# Daughter2_routed.net
KiCad netlist of a schematic drawn in EAGLE
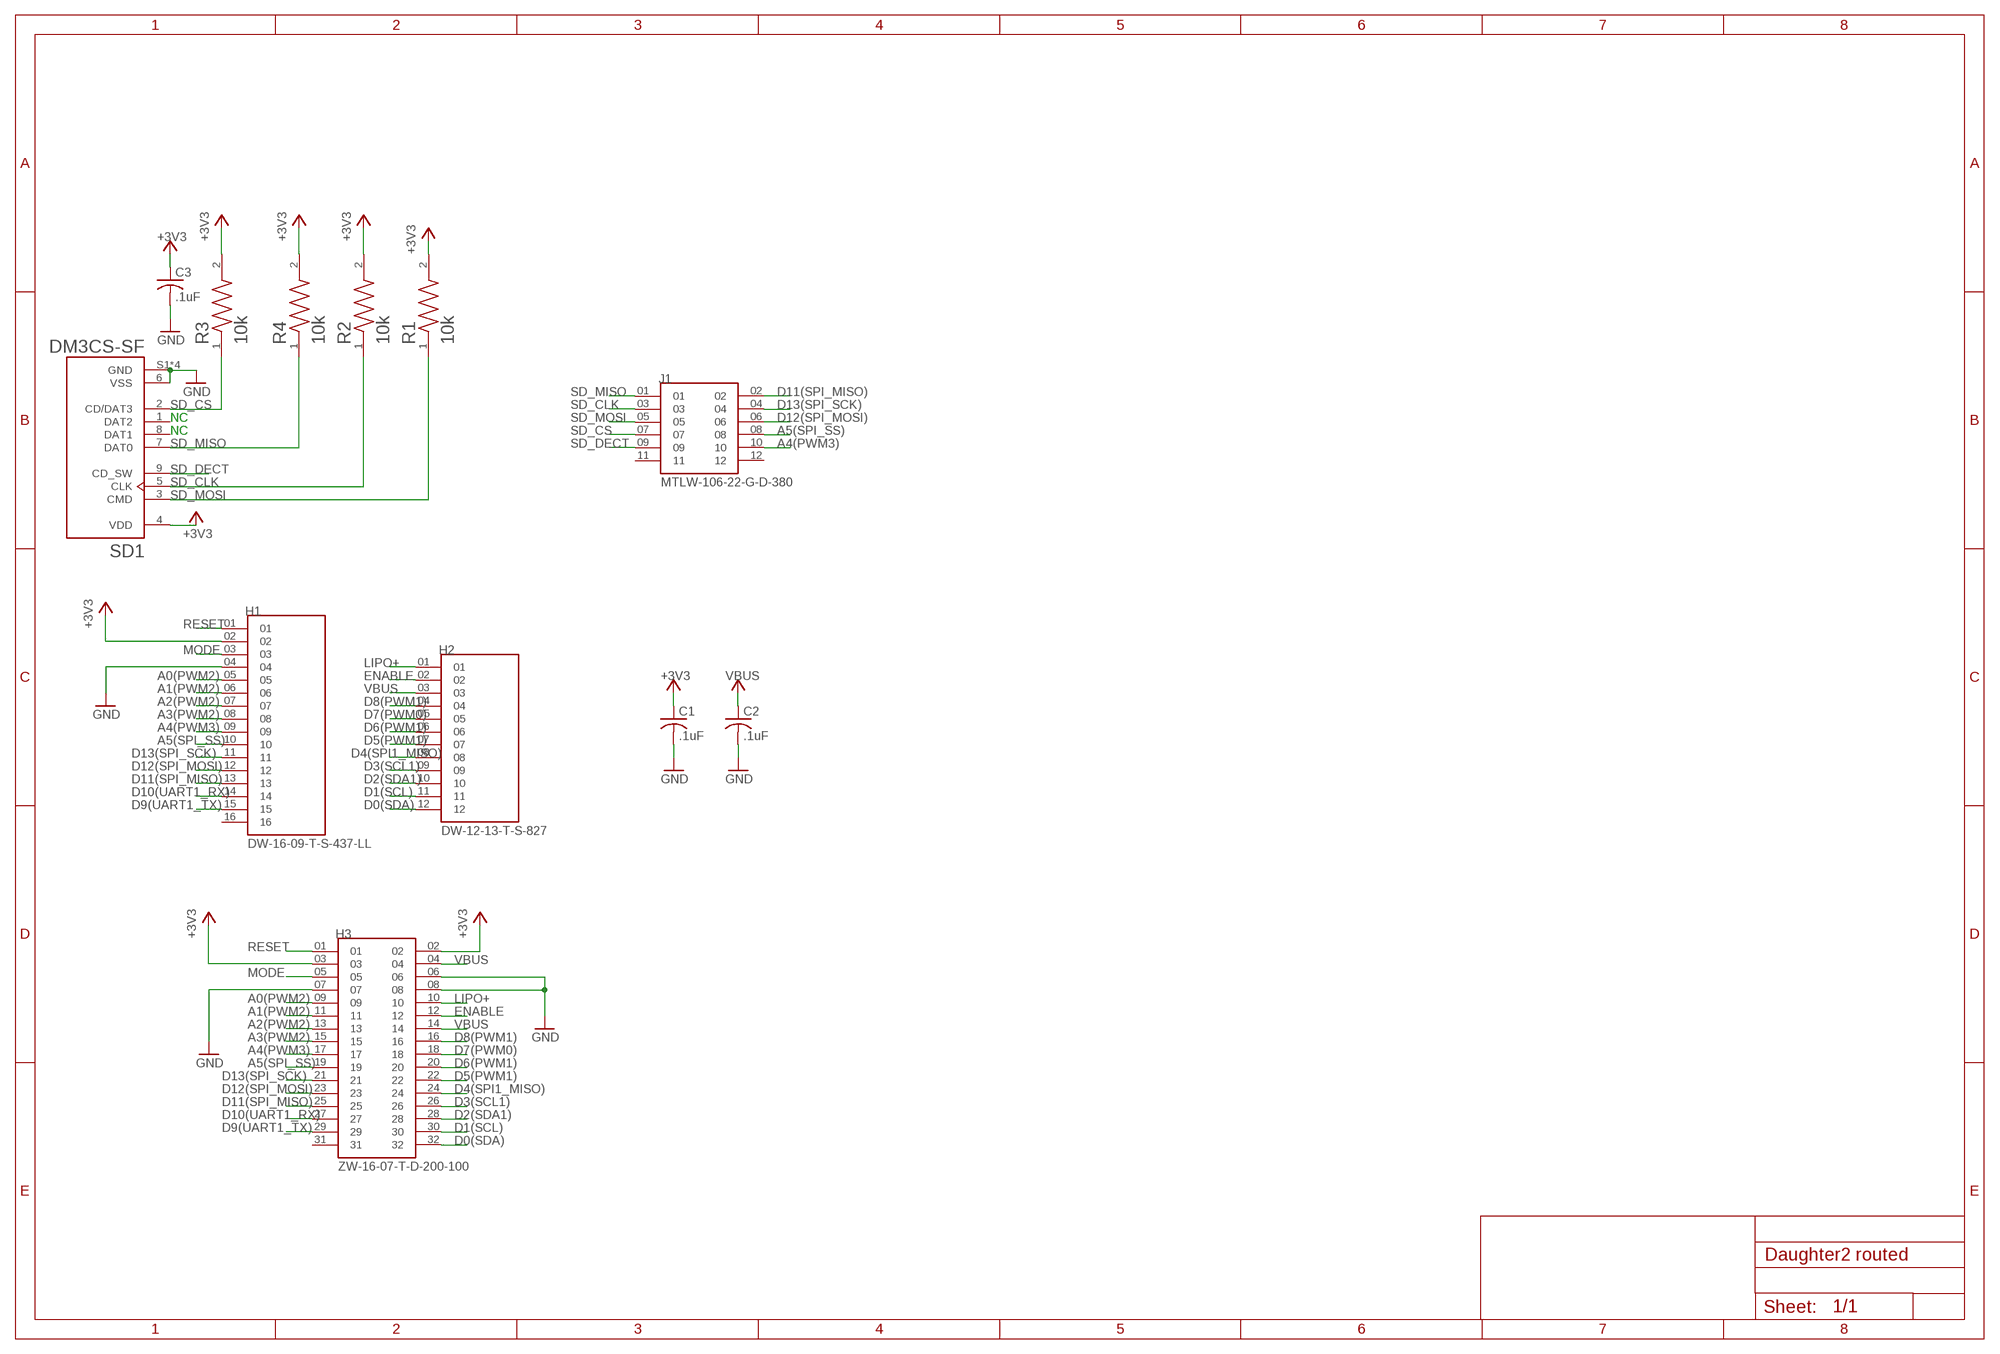
[diagram p0: schematic, sheet 1]

(export (version "E")
  (design (tool "Eeschema 10.0.6"))
  (components
    (comp (ref "C1")
      (value ".1uF")
      (footprint "eagle-import:C025-030X050")
      (libsource (lib "eagle-import") (part "C-US025-030X050"))
    )
    (comp (ref "C2")
      (value ".1uF")
      (footprint "eagle-import:C025-030X050")
      (libsource (lib "eagle-import") (part "C-US025-030X050"))
    )
    (comp (ref "C3")
      (value ".1uF")
      (footprint "eagle-import:C025-030X050")
      (libsource (lib "eagle-import") (part "C-US025-030X050"))
    )
    (comp (ref "H1")
      (value "DW-16-09-T-S-437-LL")
      (footprint "eagle-import:SAMTEC_DW-16-09-T-S-437-LL")
      (fields (field (name "MF") "Samtec"))
      (libsource (lib "eagle-import") (part "DW-16-09-T-S-437-LL"))
    )
    (comp (ref "H2")
      (value "DW-12-13-T-S-827")
      (footprint "eagle-import:SAMTEC_DW-12-13-T-S-827")
      (fields (field (name "MF") "Samtec Inc."))
      (libsource (lib "eagle-import") (part "DW-12-13-T-S-827"))
    )
    (comp (ref "H3")
      (value "ZW-16-07-T-D-200-100")
      (footprint "eagle-import:SAMTEC_ZW-16-07-T-D-200-100")
      (fields (field (name "MF") "Samtec Inc."))
      (libsource (lib "eagle-import") (part "ZW-16-07-T-D-200-100"))
    )
    (comp (ref "J1")
      (value "MTLW-106-22-G-D-380")
      (footprint "eagle-import:SAMTEC_MTLW-106-22-G-D-380")
      (fields (field (name "MF") "Samtec"))
      (libsource (lib "eagle-import") (part "MTLW-106-22-G-D-380"))
    )
    (comp (ref "R1")
      (value "10k")
      (footprint "eagle-import:RESAD700W45L350D185")
      (fields
        (field (name "COMMENT") "1623927-4")
        (field (name "MF") "TE Connectivity")
        (field (name "TOLERANCE") "5%")
      )
      (libsource (lib "eagle-import") (part "1623927-4"))
    )
    (comp (ref "R2")
      (value "10k")
      (footprint "eagle-import:RESAD700W45L350D185")
      (fields
        (field (name "COMMENT") "1623927-4")
        (field (name "MF") "TE Connectivity")
        (field (name "TOLERANCE") "5%")
      )
      (libsource (lib "eagle-import") (part "1623927-4"))
    )
    (comp (ref "R3")
      (value "10k")
      (footprint "eagle-import:RESAD700W45L350D185")
      (fields
        (field (name "COMMENT") "1623927-4")
        (field (name "MF") "TE Connectivity")
        (field (name "TOLERANCE") "5%")
      )
      (libsource (lib "eagle-import") (part "1623927-4"))
    )
    (comp (ref "R4")
      (value "10k")
      (footprint "eagle-import:RESAD700W45L350D185")
      (fields
        (field (name "COMMENT") "1623927-4")
        (field (name "MF") "TE Connectivity")
        (field (name "TOLERANCE") "5%")
      )
      (libsource (lib "eagle-import") (part "1623927-4"))
    )
    (comp (ref "SD1")
      (value "DM3CS-SF")
      (footprint "eagle-import:HRS_DM3CS-SF")
      (fields (field (name "MF") "Hirose"))
      (libsource (lib "eagle-import") (part "DM3CS-SF"))
    )
  )
  (nets
    (net (code "1") (name "+3V3") (class "Default")
      (node (ref "C1") (pin "1") (pinfunction "1_1") (pintype "passive"))
      (node (ref "C3") (pin "1") (pinfunction "1_1") (pintype "passive"))
      (node (ref "H1") (pin "02") (pinfunction "02_02") (pintype "passive"))
      (node (ref "H3") (pin "02") (pinfunction "02_02") (pintype "passive"))
      (node (ref "H3") (pin "03") (pinfunction "03_03") (pintype "passive"))
      (node (ref "R1") (pin "2") (pinfunction "2_2") (pintype "passive"))
      (node (ref "R2") (pin "2") (pinfunction "2_2") (pintype "passive"))
      (node (ref "R3") (pin "2") (pinfunction "2_2") (pintype "passive"))
      (node (ref "R4") (pin "2") (pinfunction "2_2") (pintype "passive"))
      (node (ref "SD1") (pin "4") (pinfunction "VDD_4") (pintype "passive"))
    )
    (net (code "2") (name "/A0(PWM2)") (class "Default")
      (node (ref "H1") (pin "05") (pinfunction "05_05") (pintype "passive"))
      (node (ref "H3") (pin "09") (pinfunction "09_09") (pintype "passive"))
    )
    (net (code "3") (name "/A1(PWM2)") (class "Default")
      (node (ref "H1") (pin "06") (pinfunction "06_06") (pintype "passive"))
      (node (ref "H3") (pin "11") (pinfunction "11_11") (pintype "passive"))
    )
    (net (code "4") (name "/A2(PWM2)") (class "Default")
      (node (ref "H1") (pin "07") (pinfunction "07_07") (pintype "passive"))
      (node (ref "H3") (pin "13") (pinfunction "13_13") (pintype "passive"))
    )
    (net (code "5") (name "/A3(PWM2)") (class "Default")
      (node (ref "H1") (pin "08") (pinfunction "08_08") (pintype "passive"))
      (node (ref "H3") (pin "15") (pinfunction "15_15") (pintype "passive"))
    )
    (net (code "6") (name "/A4(PWM3)") (class "Default")
      (node (ref "H1") (pin "09") (pinfunction "09_09") (pintype "passive"))
      (node (ref "H3") (pin "17") (pinfunction "17_17") (pintype "passive"))
      (node (ref "J1") (pin "10") (pinfunction "10_10") (pintype "passive"))
    )
    (net (code "7") (name "/A5(SPI_SS)") (class "Default")
      (node (ref "H1") (pin "10") (pinfunction "10_10") (pintype "passive"))
      (node (ref "H3") (pin "19") (pinfunction "19_19") (pintype "passive"))
      (node (ref "J1") (pin "08") (pinfunction "08_08") (pintype "passive"))
    )
    (net (code "8") (name "/D0(SDA)") (class "Default")
      (node (ref "H2") (pin "12") (pinfunction "12_12") (pintype "passive"))
      (node (ref "H3") (pin "32") (pinfunction "32_32") (pintype "passive"))
    )
    (net (code "9") (name "/D1(SCL)") (class "Default")
      (node (ref "H2") (pin "11") (pinfunction "11_11") (pintype "passive"))
      (node (ref "H3") (pin "30") (pinfunction "30_30") (pintype "passive"))
    )
    (net (code "10") (name "/D2(SDA1)") (class "Default")
      (node (ref "H2") (pin "10") (pinfunction "10_10") (pintype "passive"))
      (node (ref "H3") (pin "28") (pinfunction "28_28") (pintype "passive"))
    )
    (net (code "11") (name "/D3(SCL1)") (class "Default")
      (node (ref "H2") (pin "09") (pinfunction "09_09") (pintype "passive"))
      (node (ref "H3") (pin "26") (pinfunction "26_26") (pintype "passive"))
    )
    (net (code "12") (name "/D4(SPI1_MISO)") (class "Default")
      (node (ref "H2") (pin "08") (pinfunction "08_08") (pintype "passive"))
      (node (ref "H3") (pin "24") (pinfunction "24_24") (pintype "passive"))
    )
    (net (code "13") (name "/D5(PWM1)") (class "Default")
      (node (ref "H2") (pin "07") (pinfunction "07_07") (pintype "passive"))
      (node (ref "H3") (pin "22") (pinfunction "22_22") (pintype "passive"))
    )
    (net (code "14") (name "/D6(PWM1)") (class "Default")
      (node (ref "H2") (pin "06") (pinfunction "06_06") (pintype "passive"))
      (node (ref "H3") (pin "20") (pinfunction "20_20") (pintype "passive"))
    )
    (net (code "15") (name "/D7(PWM0)") (class "Default")
      (node (ref "H2") (pin "05") (pinfunction "05_05") (pintype "passive"))
      (node (ref "H3") (pin "18") (pinfunction "18_18") (pintype "passive"))
    )
    (net (code "16") (name "/D8(PWM1)") (class "Default")
      (node (ref "H2") (pin "04") (pinfunction "04_04") (pintype "passive"))
      (node (ref "H3") (pin "16") (pinfunction "16_16") (pintype "passive"))
    )
    (net (code "17") (name "/D9(UART1_TX)") (class "Default")
      (node (ref "H1") (pin "15") (pinfunction "15_15") (pintype "passive"))
      (node (ref "H3") (pin "29") (pinfunction "29_29") (pintype "passive"))
    )
    (net (code "18") (name "/D10(UART1_RX)") (class "Default")
      (node (ref "H1") (pin "14") (pinfunction "14_14") (pintype "passive"))
      (node (ref "H3") (pin "27") (pinfunction "27_27") (pintype "passive"))
    )
    (net (code "19") (name "/D11(SPI_MISO)") (class "Default")
      (node (ref "H1") (pin "13") (pinfunction "13_13") (pintype "passive"))
      (node (ref "H3") (pin "25") (pinfunction "25_25") (pintype "passive"))
      (node (ref "J1") (pin "02") (pinfunction "02_02") (pintype "passive"))
    )
    (net (code "20") (name "/D12(SPI_MOSI)") (class "Default")
      (node (ref "H1") (pin "12") (pinfunction "12_12") (pintype "passive"))
      (node (ref "H3") (pin "23") (pinfunction "23_23") (pintype "passive"))
      (node (ref "J1") (pin "06") (pinfunction "06_06") (pintype "passive"))
    )
    (net (code "21") (name "/D13(SPI_SCK)") (class "Default")
      (node (ref "H1") (pin "11") (pinfunction "11_11") (pintype "passive"))
      (node (ref "H3") (pin "21") (pinfunction "21_21") (pintype "passive"))
      (node (ref "J1") (pin "04") (pinfunction "04_04") (pintype "passive"))
    )
    (net (code "22") (name "/ENABLE") (class "Default")
      (node (ref "H2") (pin "02") (pinfunction "02_02") (pintype "passive"))
      (node (ref "H3") (pin "12") (pinfunction "12_12") (pintype "passive"))
    )
    (net (code "23") (name "/LIPO+") (class "Default")
      (node (ref "H2") (pin "01") (pinfunction "01_01") (pintype "passive"))
      (node (ref "H3") (pin "10") (pinfunction "10_10") (pintype "passive"))
    )
    (net (code "24") (name "/MODE") (class "Default")
      (node (ref "H1") (pin "03") (pinfunction "03_03") (pintype "passive"))
      (node (ref "H3") (pin "05") (pinfunction "05_05") (pintype "passive"))
    )
    (net (code "25") (name "/RESET") (class "Default")
      (node (ref "H1") (pin "01") (pinfunction "01_01") (pintype "passive"))
      (node (ref "H3") (pin "01") (pinfunction "01_01") (pintype "passive"))
    )
    (net (code "26") (name "/SD_CLK") (class "Default")
      (node (ref "J1") (pin "03") (pinfunction "03_03") (pintype "passive"))
      (node (ref "R2") (pin "1") (pinfunction "1_1") (pintype "passive"))
      (node (ref "SD1") (pin "5") (pinfunction "CLK_5") (pintype "passive"))
    )
    (net (code "27") (name "/SD_CS") (class "Default")
      (node (ref "J1") (pin "07") (pinfunction "07_07") (pintype "passive"))
      (node (ref "R3") (pin "1") (pinfunction "1_1") (pintype "passive"))
      (node (ref "SD1") (pin "2") (pinfunction "CD/DAT3_2") (pintype "passive"))
    )
    (net (code "28") (name "/SD_DECT") (class "Default")
      (node (ref "J1") (pin "09") (pinfunction "09_09") (pintype "passive"))
      (node (ref "SD1") (pin "9") (pinfunction "CD_SW_9") (pintype "passive"))
    )
    (net (code "29") (name "/SD_MISO") (class "Default")
      (node (ref "J1") (pin "01") (pinfunction "01_01") (pintype "passive"))
      (node (ref "R4") (pin "1") (pinfunction "1_1") (pintype "passive"))
      (node (ref "SD1") (pin "7") (pinfunction "DAT0_7") (pintype "passive"))
    )
    (net (code "30") (name "/SD_MOSI") (class "Default")
      (node (ref "J1") (pin "05") (pinfunction "05_05") (pintype "passive"))
      (node (ref "R1") (pin "1") (pinfunction "1_1") (pintype "passive"))
      (node (ref "SD1") (pin "3") (pinfunction "CMD_3") (pintype "passive"))
    )
    (net (code "31") (name "GND") (class "Default")
      (node (ref "C1") (pin "2") (pinfunction "2_2") (pintype "passive"))
      (node (ref "C2") (pin "2") (pinfunction "2_2") (pintype "passive"))
      (node (ref "C3") (pin "2") (pinfunction "2_2") (pintype "passive"))
      (node (ref "H1") (pin "04") (pinfunction "04_04") (pintype "passive"))
      (node (ref "H3") (pin "06") (pinfunction "06_06") (pintype "passive"))
      (node (ref "H3") (pin "07") (pinfunction "07_07") (pintype "passive"))
      (node (ref "H3") (pin "08") (pinfunction "08_08") (pintype "passive"))
      (node (ref "SD1") (pin "6") (pinfunction "VSS_6") (pintype "passive"))
      (node (ref "SD1") (pin "S1") (pinfunction "GND_S1") (pintype "passive"))
      (node (ref "SD1") (pin "S2") (pinfunction "GND_S2") (pintype "passive"))
      (node (ref "SD1") (pin "S3") (pinfunction "GND_S3") (pintype "passive"))
      (node (ref "SD1") (pin "S5") (pinfunction "GND_S5") (pintype "passive"))
    )
    (net (code "32") (name "VCC") (class "Default")
      (node (ref "C2") (pin "1") (pinfunction "1_1") (pintype "passive"))
      (node (ref "H2") (pin "03") (pinfunction "03_03") (pintype "passive"))
      (node (ref "H3") (pin "04") (pinfunction "04_04") (pintype "passive"))
      (node (ref "H3") (pin "14") (pinfunction "14_14") (pintype "passive"))
    )
    (net (code "33") (name "unconnected-(H1-Pad16)") (class "Default")
      (node (ref "H1") (pin "16") (pinfunction "16_16") (pintype "passive"))
    )
    (net (code "34") (name "unconnected-(H3-Pad31)") (class "Default")
      (node (ref "H3") (pin "31") (pinfunction "31_31") (pintype "passive"))
    )
    (net (code "35") (name "unconnected-(J1-Pad11)") (class "Default")
      (node (ref "J1") (pin "11") (pinfunction "11_11") (pintype "passive"))
    )
    (net (code "36") (name "unconnected-(J1-Pad12)") (class "Default")
      (node (ref "J1") (pin "12") (pinfunction "12_12") (pintype "passive"))
    )
    (net (code "37") (name "unconnected-(SD1-DAT1-Pad8)") (class "Default")
      (node (ref "SD1") (pin "8") (pinfunction "DAT1_8") (pintype "passive"))
    )
    (net (code "38") (name "unconnected-(SD1-DAT2-Pad1)") (class "Default")
      (node (ref "SD1") (pin "1") (pinfunction "DAT2_1") (pintype "passive"))
    )
  )
)
